# th-usb.net
KiCad netlist of a schematic drawn in EAGLE
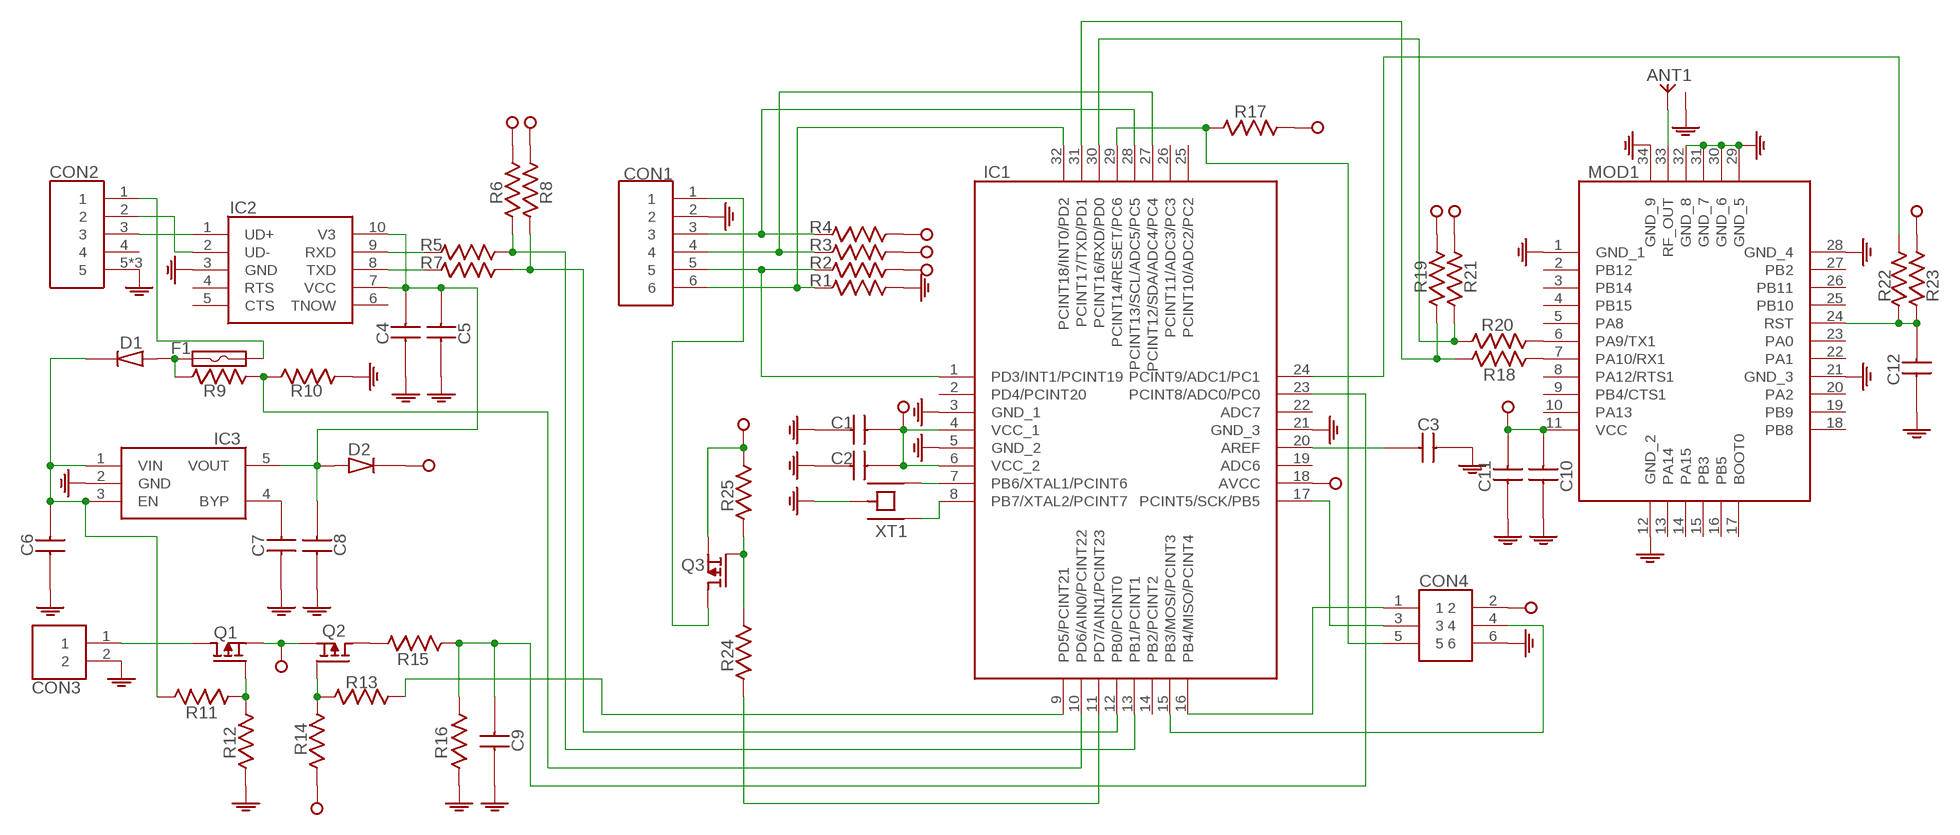
[diagram p0: schematic, sheet 1]

(export (version "E")
  (design (tool "Eeschema 10.0.6"))
  (components
    (comp (ref "ANT1")
      (value "SMA-RF")
      (footprint "eagle-import:SMA-RF")
      (libsource (lib "eagle-import") (part "SMA-RF"))
    )
    (comp (ref "C1")
      (value "CAPACITOR-0805")
      (footprint "eagle-import:0805")
      (libsource (lib "eagle-import") (part "CAPACITOR-0805"))
    )
    (comp (ref "C2")
      (value "CAPACITOR-0603")
      (footprint "eagle-import:0603")
      (libsource (lib "eagle-import") (part "CAPACITOR-0603"))
    )
    (comp (ref "C3")
      (value "CAPACITOR-0603")
      (footprint "eagle-import:0603")
      (libsource (lib "eagle-import") (part "CAPACITOR-0603"))
    )
    (comp (ref "C4")
      (value "CAPACITOR-0805")
      (footprint "eagle-import:0805")
      (libsource (lib "eagle-import") (part "CAPACITOR-0805"))
    )
    (comp (ref "C5")
      (value "CAPACITOR-0603")
      (footprint "eagle-import:0603")
      (libsource (lib "eagle-import") (part "CAPACITOR-0603"))
    )
    (comp (ref "C6")
      (value "CAPACITOR-0805")
      (footprint "eagle-import:0805")
      (libsource (lib "eagle-import") (part "CAPACITOR-0805"))
    )
    (comp (ref "C7")
      (value "CAPACITOR-0603")
      (footprint "eagle-import:0603")
      (libsource (lib "eagle-import") (part "CAPACITOR-0603"))
    )
    (comp (ref "C8")
      (value "CAPACITOR-0805")
      (footprint "eagle-import:0805")
      (libsource (lib "eagle-import") (part "CAPACITOR-0805"))
    )
    (comp (ref "C9")
      (value "CAPACITOR-0603")
      (footprint "eagle-import:0603")
      (libsource (lib "eagle-import") (part "CAPACITOR-0603"))
    )
    (comp (ref "C10")
      (value "CAPACITOR-0805")
      (footprint "eagle-import:0805")
      (libsource (lib "eagle-import") (part "CAPACITOR-0805"))
    )
    (comp (ref "C11")
      (value "CAPACITOR-0603")
      (footprint "eagle-import:0603")
      (libsource (lib "eagle-import") (part "CAPACITOR-0603"))
    )
    (comp (ref "C12")
      (value "CAPACITOR-0603")
      (footprint "eagle-import:0603")
      (libsource (lib "eagle-import") (part "CAPACITOR-0603"))
    )
    (comp (ref "CON1")
      (value "CON-6P-3_81-PLUG")
      (footprint "eagle-import:CON-6P-3_81-PLUG")
      (libsource (lib "eagle-import") (part "CON-6P-3_81-PLUG"))
    )
    (comp (ref "CON2")
      (value "USB-MICRO-DIP-VER")
      (footprint "eagle-import:USB-MICRO-DIP-VER")
      (libsource (lib "eagle-import") (part "USB-MICRO-DIP-VER"))
    )
    (comp (ref "CON3")
      (value "JST-PH-2-2.0MM")
      (footprint "eagle-import:JST-PH-2-2.0MM")
      (libsource (lib "eagle-import") (part "JST-PH-2-2.0MM"))
    )
    (comp (ref "CON4")
      (value "ISP")
      (footprint "eagle-import:ISP")
      (libsource (lib "eagle-import") (part "ISP"))
    )
    (comp (ref "D1")
      (value "DIODE-SOD123")
      (footprint "eagle-import:SOD123-DIODE")
      (libsource (lib "eagle-import") (part "DIODE-SOD123"))
    )
    (comp (ref "D2")
      (value "DIODE-SOD123")
      (footprint "eagle-import:SOD123-DIODE")
      (libsource (lib "eagle-import") (part "DIODE-SOD123"))
    )
    (comp (ref "F1")
      (value "FUSE-0805")
      (footprint "eagle-import:0805")
      (libsource (lib "eagle-import") (part "FUSE-0805"))
    )
    (comp (ref "IC1")
      (value "ATMEGA328P-AU")
      (footprint "eagle-import:TQFP-32")
      (libsource (lib "eagle-import") (part "ATMEGA328P-AU"))
    )
    (comp (ref "IC2")
      (value "CH340E")
      (footprint "eagle-import:MSOP-10")
      (libsource (lib "eagle-import") (part "CH340E"))
    )
    (comp (ref "IC3")
      (value "MIC5219")
      (footprint "eagle-import:SOT23-5")
      (libsource (lib "eagle-import") (part "MIC5219"))
    )
    (comp (ref "MOD1")
      (value "RAK811")
      (footprint "eagle-import:RAK811")
      (libsource (lib "eagle-import") (part "RAK811"))
    )
    (comp (ref "Q1")
      (value "P-MOSFET")
      (footprint "eagle-import:SOT23-3")
      (libsource (lib "eagle-import") (part "P-MOSFET"))
    )
    (comp (ref "Q2")
      (value "P-MOSFET")
      (footprint "eagle-import:SOT23-3")
      (libsource (lib "eagle-import") (part "P-MOSFET"))
    )
    (comp (ref "Q3")
      (value "P-MOSFET")
      (footprint "eagle-import:SOT23-3")
      (libsource (lib "eagle-import") (part "P-MOSFET"))
    )
    (comp (ref "R1")
      (value "RESISTOR-0603")
      (footprint "eagle-import:0603")
      (libsource (lib "eagle-import") (part "RESISTOR-0603"))
    )
    (comp (ref "R2")
      (value "RESISTOR-0603")
      (footprint "eagle-import:0603")
      (libsource (lib "eagle-import") (part "RESISTOR-0603"))
    )
    (comp (ref "R3")
      (value "RESISTOR-0603")
      (footprint "eagle-import:0603")
      (libsource (lib "eagle-import") (part "RESISTOR-0603"))
    )
    (comp (ref "R4")
      (value "RESISTOR-0603")
      (footprint "eagle-import:0603")
      (libsource (lib "eagle-import") (part "RESISTOR-0603"))
    )
    (comp (ref "R5")
      (value "RESISTOR-0603")
      (footprint "eagle-import:0603")
      (libsource (lib "eagle-import") (part "RESISTOR-0603"))
    )
    (comp (ref "R6")
      (value "RESISTOR-0603")
      (footprint "eagle-import:0603")
      (libsource (lib "eagle-import") (part "RESISTOR-0603"))
    )
    (comp (ref "R7")
      (value "RESISTOR-0603")
      (footprint "eagle-import:0603")
      (libsource (lib "eagle-import") (part "RESISTOR-0603"))
    )
    (comp (ref "R8")
      (value "RESISTOR-0603")
      (footprint "eagle-import:0603")
      (libsource (lib "eagle-import") (part "RESISTOR-0603"))
    )
    (comp (ref "R9")
      (value "RESISTOR-0603")
      (footprint "eagle-import:0603")
      (libsource (lib "eagle-import") (part "RESISTOR-0603"))
    )
    (comp (ref "R10")
      (value "RESISTOR-0603")
      (footprint "eagle-import:0603")
      (libsource (lib "eagle-import") (part "RESISTOR-0603"))
    )
    (comp (ref "R11")
      (value "RESISTOR-0603")
      (footprint "eagle-import:0603")
      (libsource (lib "eagle-import") (part "RESISTOR-0603"))
    )
    (comp (ref "R12")
      (value "RESISTOR-0603")
      (footprint "eagle-import:0603")
      (libsource (lib "eagle-import") (part "RESISTOR-0603"))
    )
    (comp (ref "R13")
      (value "RESISTOR-0603")
      (footprint "eagle-import:0603")
      (libsource (lib "eagle-import") (part "RESISTOR-0603"))
    )
    (comp (ref "R14")
      (value "RESISTOR-0603")
      (footprint "eagle-import:0603")
      (libsource (lib "eagle-import") (part "RESISTOR-0603"))
    )
    (comp (ref "R15")
      (value "RESISTOR-0603")
      (footprint "eagle-import:0603")
      (libsource (lib "eagle-import") (part "RESISTOR-0603"))
    )
    (comp (ref "R16")
      (value "RESISTOR-0603")
      (footprint "eagle-import:0603")
      (libsource (lib "eagle-import") (part "RESISTOR-0603"))
    )
    (comp (ref "R17")
      (value "RESISTOR-0603")
      (footprint "eagle-import:0603")
      (libsource (lib "eagle-import") (part "RESISTOR-0603"))
    )
    (comp (ref "R18")
      (value "RESISTOR-0603")
      (footprint "eagle-import:0603")
      (libsource (lib "eagle-import") (part "RESISTOR-0603"))
    )
    (comp (ref "R19")
      (value "RESISTOR-0603")
      (footprint "eagle-import:0603")
      (libsource (lib "eagle-import") (part "RESISTOR-0603"))
    )
    (comp (ref "R20")
      (value "RESISTOR-0603")
      (footprint "eagle-import:0603")
      (libsource (lib "eagle-import") (part "RESISTOR-0603"))
    )
    (comp (ref "R21")
      (value "RESISTOR-0603")
      (footprint "eagle-import:0603")
      (libsource (lib "eagle-import") (part "RESISTOR-0603"))
    )
    (comp (ref "R22")
      (value "RESISTOR-0603")
      (footprint "eagle-import:0603")
      (libsource (lib "eagle-import") (part "RESISTOR-0603"))
    )
    (comp (ref "R23")
      (value "RESISTOR-0603")
      (footprint "eagle-import:0603")
      (libsource (lib "eagle-import") (part "RESISTOR-0603"))
    )
    (comp (ref "R24")
      (value "RESISTOR-0603")
      (footprint "eagle-import:0603")
      (libsource (lib "eagle-import") (part "RESISTOR-0603"))
    )
    (comp (ref "R25")
      (value "RESISTOR-0603")
      (footprint "eagle-import:0603")
      (libsource (lib "eagle-import") (part "RESISTOR-0603"))
    )
    (comp (ref "XT1")
      (value "RESONATOR-3215")
      (footprint "eagle-import:RESONATOR-3215")
      (libsource (lib "eagle-import") (part "RESONATOR-3215"))
    )
  )
  (nets
    (net (code "1") (name "/PD4{slash}PCINT20") (class "Default")
      (node (ref "IC1") (pin "2") (pinfunction "PD4/PCINT20_2") (pintype "power_in"))
    )
    (net (code "2") (name "GND") (class "Default")
      (node (ref "ANT1") (pin "2") (pinfunction "GND_2") (pintype "power_in"))
      (node (ref "ANT1") (pin "3") (pinfunction "GND_3") (pintype "power_in"))
      (node (ref "ANT1") (pin "4") (pinfunction "GND_4") (pintype "power_in"))
      (node (ref "ANT1") (pin "5") (pinfunction "GND_5") (pintype "power_in"))
      (node (ref "C1") (pin "1") (pinfunction "1_1") (pintype "passive"))
      (node (ref "C10") (pin "1") (pinfunction "1_1") (pintype "passive"))
      (node (ref "C11") (pin "1") (pinfunction "1_1") (pintype "passive"))
      (node (ref "C12") (pin "1") (pinfunction "1_1") (pintype "passive"))
      (node (ref "C2") (pin "1") (pinfunction "1_1") (pintype "passive"))
      (node (ref "C3") (pin "2") (pinfunction "2_2") (pintype "passive"))
      (node (ref "C4") (pin "1") (pinfunction "1_1") (pintype "passive"))
      (node (ref "C5") (pin "1") (pinfunction "1_1") (pintype "passive"))
      (node (ref "C6") (pin "1") (pinfunction "1_1") (pintype "passive"))
      (node (ref "C7") (pin "2") (pinfunction "2_2") (pintype "passive"))
      (node (ref "C8") (pin "1") (pinfunction "1_1") (pintype "passive"))
      (node (ref "C9") (pin "1") (pinfunction "1_1") (pintype "passive"))
      (node (ref "CON1") (pin "2") (pinfunction "2_2") (pintype "bidirectional"))
      (node (ref "CON2") (pin "5") (pinfunction "5_5") (pintype "bidirectional"))
      (node (ref "CON2") (pin "6") (pinfunction "5_6") (pintype "bidirectional"))
      (node (ref "CON2") (pin "7") (pinfunction "5_7") (pintype "bidirectional"))
      (node (ref "CON3") (pin "2") (pinfunction "2_2") (pintype "bidirectional"))
      (node (ref "CON4") (pin "6") (pinfunction "6_6") (pintype "power_in"))
      (node (ref "IC1") (pin "21") (pinfunction "GND_3_21") (pintype "power_in"))
      (node (ref "IC1") (pin "3") (pinfunction "GND_1_3") (pintype "power_in"))
      (node (ref "IC1") (pin "5") (pinfunction "GND_2_5") (pintype "power_in"))
      (node (ref "IC2") (pin "3") (pinfunction "GND_3") (pintype "power_in"))
      (node (ref "IC3") (pin "2") (pinfunction "GND_2") (pintype "power_in"))
      (node (ref "MOD1") (pin "1") (pinfunction "GND_1_1") (pintype "power_in"))
      (node (ref "MOD1") (pin "12") (pinfunction "GND_2_12") (pintype "power_in"))
      (node (ref "MOD1") (pin "21") (pinfunction "GND_3_21") (pintype "power_in"))
      (node (ref "MOD1") (pin "28") (pinfunction "GND_4_28") (pintype "power_in"))
      (node (ref "MOD1") (pin "29") (pinfunction "GND_5_29") (pintype "power_in"))
      (node (ref "MOD1") (pin "30") (pinfunction "GND_6_30") (pintype "power_in"))
      (node (ref "MOD1") (pin "31") (pinfunction "GND_7_31") (pintype "power_in"))
      (node (ref "MOD1") (pin "32") (pinfunction "GND_8_32") (pintype "power_in"))
      (node (ref "MOD1") (pin "34") (pinfunction "GND_9_34") (pintype "power_in"))
      (node (ref "R1") (pin "2") (pinfunction "2_2") (pintype "passive"))
      (node (ref "R10") (pin "1") (pinfunction "1_1") (pintype "passive"))
      (node (ref "R12") (pin "1") (pinfunction "1_1") (pintype "passive"))
      (node (ref "R16") (pin "1") (pinfunction "1_1") (pintype "passive"))
      (node (ref "XT1") (pin "3") (pinfunction "3_3") (pintype "power_in"))
    )
    (net (code "3") (name "Net-(ANT1-ANT)") (class "Default")
      (node (ref "ANT1") (pin "1") (pinfunction "ANT_1") (pintype "bidirectional"))
      (node (ref "MOD1") (pin "33") (pinfunction "RF_OUT_33") (pintype "bidirectional"))
    )
    (net (code "4") (name "Net-(CON2-Pad1)") (class "Default")
      (node (ref "CON2") (pin "1") (pinfunction "1_1") (pintype "bidirectional"))
      (node (ref "F1") (pin "1") (pinfunction "1_1") (pintype "passive"))
    )
    (net (code "5") (name "Net-(D1-A)") (class "Default")
      (node (ref "D1") (pin "2") (pinfunction "A_2") (pintype "bidirectional"))
      (node (ref "F1") (pin "2") (pinfunction "2_2") (pintype "passive"))
      (node (ref "R9") (pin "1") (pinfunction "1_1") (pintype "passive"))
    )
    (net (code "6") (name "Net-(D1-K)") (class "Default")
      (node (ref "C6") (pin "2") (pinfunction "2_2") (pintype "passive"))
      (node (ref "D1") (pin "1") (pinfunction "K_1") (pintype "bidirectional"))
      (node (ref "IC3") (pin "1") (pinfunction "VIN_1") (pintype "power_in"))
      (node (ref "IC3") (pin "3") (pinfunction "EN_3") (pintype "input"))
      (node (ref "R11") (pin "2") (pinfunction "2_2") (pintype "passive"))
    )
    (net (code "7") (name "Net-(D2-A)") (class "Default")
      (node (ref "C4") (pin "2") (pinfunction "2_2") (pintype "passive"))
      (node (ref "C5") (pin "2") (pinfunction "2_2") (pintype "passive"))
      (node (ref "C8") (pin "2") (pinfunction "2_2") (pintype "passive"))
      (node (ref "D2") (pin "2") (pinfunction "A_2") (pintype "bidirectional"))
      (node (ref "IC2") (pin "10") (pinfunction "V3_10") (pintype "power_in"))
      (node (ref "IC2") (pin "7") (pinfunction "VCC_7") (pintype "power_in"))
      (node (ref "IC3") (pin "5") (pinfunction "VOUT_5") (pintype "power_in"))
    )
    (net (code "8") (name "Net-(IC1-AREF)") (class "Default")
      (node (ref "C3") (pin "1") (pinfunction "1_1") (pintype "passive"))
      (node (ref "IC1") (pin "20") (pinfunction "AREF_20") (pintype "bidirectional"))
    )
    (net (code "9") (name "Net-(IC1-PB0{slash}PCINT0)") (class "Default")
      (node (ref "IC1") (pin "12") (pinfunction "PB0/PCINT0_12") (pintype "bidirectional"))
      (node (ref "R7") (pin "2") (pinfunction "2_2") (pintype "passive"))
      (node (ref "R8") (pin "1") (pinfunction "1_1") (pintype "passive"))
    )
    (net (code "10") (name "Net-(IC1-PB1{slash}PCINT1)") (class "Default")
      (node (ref "IC1") (pin "13") (pinfunction "PB1/PCINT1_13") (pintype "bidirectional"))
      (node (ref "R5") (pin "2") (pinfunction "2_2") (pintype "passive"))
      (node (ref "R6") (pin "1") (pinfunction "1_1") (pintype "passive"))
    )
    (net (code "11") (name "Net-(IC1-PB3{slash}MOSI{slash}PCINT3)") (class "Default")
      (node (ref "CON4") (pin "4") (pinfunction "4_4") (pintype "bidirectional"))
      (node (ref "IC1") (pin "15") (pinfunction "PB3/MOSI/PCINT3_15") (pintype "bidirectional"))
    )
    (net (code "12") (name "Net-(IC1-PB4{slash}MISO{slash}PCINT4)") (class "Default")
      (node (ref "CON4") (pin "1") (pinfunction "1_1") (pintype "bidirectional"))
      (node (ref "IC1") (pin "16") (pinfunction "PB4/MISO/PCINT4_16") (pintype "bidirectional"))
    )
    (net (code "13") (name "Net-(IC1-PB6{slash}XTAL1{slash}PCINT6)") (class "Default")
      (node (ref "IC1") (pin "7") (pinfunction "PB6/XTAL1/PCINT6_7") (pintype "bidirectional"))
      (node (ref "XT1") (pin "1") (pinfunction "1_1") (pintype "bidirectional"))
    )
    (net (code "14") (name "Net-(IC1-PB7{slash}XTAL2{slash}PCINT7)") (class "Default")
      (node (ref "IC1") (pin "8") (pinfunction "PB7/XTAL2/PCINT7_8") (pintype "bidirectional"))
      (node (ref "XT1") (pin "2") (pinfunction "2_2") (pintype "bidirectional"))
    )
    (net (code "15") (name "Net-(IC1-PCINT5{slash}SCK{slash}PB5)") (class "Default")
      (node (ref "CON4") (pin "3") (pinfunction "3_3") (pintype "bidirectional"))
      (node (ref "IC1") (pin "17") (pinfunction "PCINT5/SCK/PB5_17") (pintype "bidirectional"))
    )
    (net (code "16") (name "Net-(IC1-PCINT8{slash}ADC0{slash}PC0)") (class "Default")
      (node (ref "C9") (pin "2") (pinfunction "2_2") (pintype "passive"))
      (node (ref "IC1") (pin "23") (pinfunction "PCINT8/ADC0/PC0_23") (pintype "bidirectional"))
      (node (ref "R15") (pin "2") (pinfunction "2_2") (pintype "passive"))
      (node (ref "R16") (pin "2") (pinfunction "2_2") (pintype "passive"))
    )
    (net (code "17") (name "Net-(IC1-PCINT9{slash}ADC1{slash}PC1)") (class "Default")
      (node (ref "IC1") (pin "24") (pinfunction "PCINT9/ADC1/PC1_24") (pintype "bidirectional"))
      (node (ref "R22") (pin "2") (pinfunction "2_2") (pintype "passive"))
    )
    (net (code "18") (name "Net-(IC1-PCINT12{slash}SDA{slash}ADC4{slash}PC4)") (class "Default")
      (node (ref "CON1") (pin "4") (pinfunction "4_4") (pintype "bidirectional"))
      (node (ref "IC1") (pin "27") (pinfunction "PCINT12/SDA/ADC4/PC4_27") (pintype "bidirectional"))
      (node (ref "R3") (pin "1") (pinfunction "1_1") (pintype "passive"))
    )
    (net (code "19") (name "Net-(IC1-PCINT13{slash}SCL{slash}ADC5{slash}PC5)") (class "Default")
      (node (ref "CON1") (pin "3") (pinfunction "3_3") (pintype "bidirectional"))
      (node (ref "IC1") (pin "28") (pinfunction "PCINT13/SCL/ADC5/PC5_28") (pintype "bidirectional"))
      (node (ref "R4") (pin "1") (pinfunction "1_1") (pintype "passive"))
    )
    (net (code "20") (name "Net-(IC1-PCINT14{slash}RESET{slash}PC6)") (class "Default")
      (node (ref "CON4") (pin "5") (pinfunction "5_5") (pintype "bidirectional"))
      (node (ref "IC1") (pin "29") (pinfunction "PCINT14/RESET/PC6_29") (pintype "bidirectional"))
      (node (ref "R17") (pin "1") (pinfunction "1_1") (pintype "passive"))
    )
    (net (code "21") (name "Net-(IC1-PCINT16{slash}RXD{slash}PD0)") (class "Default")
      (node (ref "IC1") (pin "30") (pinfunction "PCINT16/RXD/PD0_30") (pintype "bidirectional"))
      (node (ref "R20") (pin "1") (pinfunction "1_1") (pintype "passive"))
      (node (ref "R21") (pin "1") (pinfunction "1_1") (pintype "passive"))
    )
    (net (code "22") (name "Net-(IC1-PCINT17{slash}TXD{slash}PD1)") (class "Default")
      (node (ref "IC1") (pin "31") (pinfunction "PCINT17/TXD/PD1_31") (pintype "bidirectional"))
      (node (ref "R18") (pin "1") (pinfunction "1_1") (pintype "passive"))
      (node (ref "R19") (pin "1") (pinfunction "1_1") (pintype "passive"))
    )
    (net (code "23") (name "Net-(IC1-PCINT18{slash}INT0{slash}PD2)") (class "Default")
      (node (ref "CON1") (pin "6") (pinfunction "6_6") (pintype "bidirectional"))
      (node (ref "IC1") (pin "32") (pinfunction "PCINT18/INT0/PD2_32") (pintype "bidirectional"))
      (node (ref "R1") (pin "1") (pinfunction "1_1") (pintype "passive"))
    )
    (net (code "24") (name "Net-(IC1-PD3{slash}INT1{slash}PCINT19)") (class "Default")
      (node (ref "CON1") (pin "5") (pinfunction "5_5") (pintype "bidirectional"))
      (node (ref "IC1") (pin "1") (pinfunction "PD3/INT1/PCINT19_1") (pintype "bidirectional"))
      (node (ref "R2") (pin "1") (pinfunction "1_1") (pintype "passive"))
    )
    (net (code "25") (name "Net-(IC1-PD5{slash}PCINT21)") (class "Default")
      (node (ref "IC1") (pin "9") (pinfunction "PD5/PCINT21_9") (pintype "bidirectional"))
      (node (ref "R13") (pin "2") (pinfunction "2_2") (pintype "passive"))
    )
    (net (code "26") (name "Net-(IC1-PD6{slash}AIN0{slash}PCINT22)") (class "Default")
      (node (ref "IC1") (pin "10") (pinfunction "PD6/AIN0/PCINT22_10") (pintype "bidirectional"))
      (node (ref "R10") (pin "2") (pinfunction "2_2") (pintype "passive"))
      (node (ref "R9") (pin "2") (pinfunction "2_2") (pintype "passive"))
    )
    (net (code "27") (name "Net-(IC1-PD7{slash}AIN1{slash}PCINT23)") (class "Default")
      (node (ref "IC1") (pin "11") (pinfunction "PD7/AIN1/PCINT23_11") (pintype "bidirectional"))
      (node (ref "R24") (pin "1") (pinfunction "1_1") (pintype "passive"))
    )
    (net (code "28") (name "Net-(IC2-RXD)") (class "Default")
      (node (ref "IC2") (pin "9") (pinfunction "RXD_9") (pintype "bidirectional"))
      (node (ref "R5") (pin "1") (pinfunction "1_1") (pintype "passive"))
    )
    (net (code "29") (name "Net-(IC2-TXD)") (class "Default")
      (node (ref "IC2") (pin "8") (pinfunction "TXD_8") (pintype "bidirectional"))
      (node (ref "R7") (pin "1") (pinfunction "1_1") (pintype "passive"))
    )
    (net (code "30") (name "Net-(IC2-UD+)") (class "Default")
      (node (ref "CON2") (pin "3") (pinfunction "3_3") (pintype "bidirectional"))
      (node (ref "IC2") (pin "1") (pinfunction "UD+_1") (pintype "power_in"))
    )
    (net (code "31") (name "Net-(IC2-UD-)") (class "Default")
      (node (ref "CON2") (pin "2") (pinfunction "2_2") (pintype "bidirectional"))
      (node (ref "IC2") (pin "2") (pinfunction "UD-_2") (pintype "power_in"))
    )
    (net (code "32") (name "Net-(IC3-BYP)") (class "Default")
      (node (ref "C7") (pin "1") (pinfunction "1_1") (pintype "passive"))
      (node (ref "IC3") (pin "4") (pinfunction "BYP_4") (pintype "output"))
    )
    (net (code "33") (name "Net-(MOD1-PA9{slash}TX1)") (class "Default")
      (node (ref "MOD1") (pin "6") (pinfunction "PA9/TX1_6") (pintype "bidirectional"))
      (node (ref "R20") (pin "2") (pinfunction "2_2") (pintype "passive"))
    )
    (net (code "34") (name "Net-(MOD1-PA10{slash}RX1)") (class "Default")
      (node (ref "MOD1") (pin "7") (pinfunction "PA10/RX1_7") (pintype "bidirectional"))
      (node (ref "R18") (pin "2") (pinfunction "2_2") (pintype "passive"))
    )
    (net (code "35") (name "Net-(MOD1-RST)") (class "Default")
      (node (ref "C12") (pin "2") (pinfunction "2_2") (pintype "passive"))
      (node (ref "MOD1") (pin "24") (pinfunction "RST_24") (pintype "bidirectional"))
      (node (ref "R22") (pin "1") (pinfunction "1_1") (pintype "passive"))
      (node (ref "R23") (pin "1") (pinfunction "1_1") (pintype "passive"))
    )
    (net (code "36") (name "Net-(Q1-D)") (class "Default")
      (node (ref "CON3") (pin "1") (pinfunction "1_1") (pintype "bidirectional"))
      (node (ref "Q1") (pin "3") (pinfunction "D_3") (pintype "bidirectional"))
    )
    (net (code "37") (name "Net-(Q1-G)") (class "Default")
      (node (ref "Q1") (pin "1") (pinfunction "G_1") (pintype "bidirectional"))
      (node (ref "R11") (pin "1") (pinfunction "1_1") (pintype "passive"))
      (node (ref "R12") (pin "2") (pinfunction "2_2") (pintype "passive"))
    )
    (net (code "38") (name "Net-(Q2-D)") (class "Default")
      (node (ref "Q2") (pin "3") (pinfunction "D_3") (pintype "bidirectional"))
      (node (ref "R15") (pin "1") (pinfunction "1_1") (pintype "passive"))
    )
    (net (code "39") (name "Net-(Q2-G)") (class "Default")
      (node (ref "Q2") (pin "1") (pinfunction "G_1") (pintype "bidirectional"))
      (node (ref "R13") (pin "1") (pinfunction "1_1") (pintype "passive"))
      (node (ref "R14") (pin "2") (pinfunction "2_2") (pintype "passive"))
    )
    (net (code "40") (name "Net-(Q3-D)") (class "Default")
      (node (ref "CON1") (pin "1") (pinfunction "1_1") (pintype "bidirectional"))
      (node (ref "Q3") (pin "3") (pinfunction "D_3") (pintype "bidirectional"))
    )
    (net (code "41") (name "Net-(Q3-G)") (class "Default")
      (node (ref "Q3") (pin "1") (pinfunction "G_1") (pintype "bidirectional"))
      (node (ref "R24") (pin "2") (pinfunction "2_2") (pintype "passive"))
      (node (ref "R25") (pin "1") (pinfunction "1_1") (pintype "passive"))
    )
    (net (code "42") (name "VCC") (class "Default")
      (node (ref "C1") (pin "2") (pinfunction "2_2") (pintype "passive"))
      (node (ref "C10") (pin "2") (pinfunction "2_2") (pintype "passive"))
      (node (ref "C11") (pin "2") (pinfunction "2_2") (pintype "passive"))
      (node (ref "C2") (pin "2") (pinfunction "2_2") (pintype "passive"))
      (node (ref "CON4") (pin "2") (pinfunction "2_2") (pintype "power_in"))
      (node (ref "D2") (pin "1") (pinfunction "K_1") (pintype "bidirectional"))
      (node (ref "IC1") (pin "18") (pinfunction "AVCC_18") (pintype "power_in"))
      (node (ref "IC1") (pin "4") (pinfunction "VCC_1_4") (pintype "power_in"))
      (node (ref "IC1") (pin "6") (pinfunction "VCC_2_6") (pintype "power_in"))
      (node (ref "MOD1") (pin "11") (pinfunction "VCC_11") (pintype "power_in"))
      (node (ref "Q1") (pin "2") (pinfunction "S_2") (pintype "bidirectional"))
      (node (ref "Q2") (pin "2") (pinfunction "S_2") (pintype "bidirectional"))
      (node (ref "Q3") (pin "2") (pinfunction "S_2") (pintype "bidirectional"))
      (node (ref "R14") (pin "1") (pinfunction "1_1") (pintype "passive"))
      (node (ref "R17") (pin "2") (pinfunction "2_2") (pintype "passive"))
      (node (ref "R19") (pin "2") (pinfunction "2_2") (pintype "passive"))
      (node (ref "R2") (pin "2") (pinfunction "2_2") (pintype "passive"))
      (node (ref "R21") (pin "2") (pinfunction "2_2") (pintype "passive"))
      (node (ref "R23") (pin "2") (pinfunction "2_2") (pintype "passive"))
      (node (ref "R25") (pin "2") (pinfunction "2_2") (pintype "passive"))
      (node (ref "R3") (pin "2") (pinfunction "2_2") (pintype "passive"))
      (node (ref "R4") (pin "2") (pinfunction "2_2") (pintype "passive"))
      (node (ref "R6") (pin "2") (pinfunction "2_2") (pintype "passive"))
      (node (ref "R8") (pin "2") (pinfunction "2_2") (pintype "passive"))
    )
    (net (code "43") (name "unconnected-(CON2-Pad4)") (class "Default")
      (node (ref "CON2") (pin "4") (pinfunction "4_4") (pintype "bidirectional"))
    )
    (net (code "44") (name "unconnected-(IC1-ADC6-Pad19)") (class "Default")
      (node (ref "IC1") (pin "19") (pinfunction "ADC6_19") (pintype "bidirectional"))
    )
    (net (code "45") (name "unconnected-(IC1-ADC7-Pad22)") (class "Default")
      (node (ref "IC1") (pin "22") (pinfunction "ADC7_22") (pintype "bidirectional"))
    )
    (net (code "46") (name "unconnected-(IC1-PB2{slash}PCINT2-Pad14)") (class "Default")
      (node (ref "IC1") (pin "14") (pinfunction "PB2/PCINT2_14") (pintype "bidirectional"))
    )
    (net (code "47") (name "unconnected-(IC1-PCINT10{slash}ADC2{slash}PC2-Pad25)") (class "Default")
      (node (ref "IC1") (pin "25") (pinfunction "PCINT10/ADC2/PC2_25") (pintype "bidirectional"))
    )
    (net (code "48") (name "unconnected-(IC1-PCINT11{slash}ADC3{slash}PC3-Pad26)") (class "Default")
      (node (ref "IC1") (pin "26") (pinfunction "PCINT11/ADC3/PC3_26") (pintype "bidirectional"))
    )
    (net (code "49") (name "unconnected-(IC2-CTS-Pad5)") (class "Default")
      (node (ref "IC2") (pin "5") (pinfunction "CTS_5") (pintype "bidirectional"))
    )
    (net (code "50") (name "unconnected-(IC2-RTS-Pad4)") (class "Default")
      (node (ref "IC2") (pin "4") (pinfunction "RTS_4") (pintype "bidirectional"))
    )
    (net (code "51") (name "unconnected-(IC2-TNOW-Pad6)") (class "Default")
      (node (ref "IC2") (pin "6") (pinfunction "TNOW_6") (pintype "bidirectional"))
    )
    (net (code "52") (name "unconnected-(MOD1-BOOT0-Pad17)") (class "Default")
      (node (ref "MOD1") (pin "17") (pinfunction "BOOT0_17") (pintype "bidirectional"))
    )
    (net (code "53") (name "unconnected-(MOD1-PA0-Pad23)") (class "Default")
      (node (ref "MOD1") (pin "23") (pinfunction "PA0_23") (pintype "bidirectional"))
    )
    (net (code "54") (name "unconnected-(MOD1-PA1-Pad22)") (class "Default")
      (node (ref "MOD1") (pin "22") (pinfunction "PA1_22") (pintype "bidirectional"))
    )
    (net (code "55") (name "unconnected-(MOD1-PA2-Pad20)") (class "Default")
      (node (ref "MOD1") (pin "20") (pinfunction "PA2_20") (pintype "bidirectional"))
    )
    (net (code "56") (name "unconnected-(MOD1-PA8-Pad5)") (class "Default")
      (node (ref "MOD1") (pin "5") (pinfunction "PA8_5") (pintype "bidirectional"))
    )
    (net (code "57") (name "unconnected-(MOD1-PA12{slash}RTS1-Pad8)") (class "Default")
      (node (ref "MOD1") (pin "8") (pinfunction "PA12/RTS1_8") (pintype "bidirectional"))
    )
    (net (code "58") (name "unconnected-(MOD1-PA13-Pad10)") (class "Default")
      (node (ref "MOD1") (pin "10") (pinfunction "PA13_10") (pintype "bidirectional"))
    )
    (net (code "59") (name "unconnected-(MOD1-PA14-Pad13)") (class "Default")
      (node (ref "MOD1") (pin "13") (pinfunction "PA14_13") (pintype "bidirectional"))
    )
    (net (code "60") (name "unconnected-(MOD1-PA15-Pad14)") (class "Default")
      (node (ref "MOD1") (pin "14") (pinfunction "PA15_14") (pintype "bidirectional"))
    )
    (net (code "61") (name "unconnected-(MOD1-PB2-Pad27)") (class "Default")
      (node (ref "MOD1") (pin "27") (pinfunction "PB2_27") (pintype "bidirectional"))
    )
    (net (code "62") (name "unconnected-(MOD1-PB3-Pad15)") (class "Default")
      (node (ref "MOD1") (pin "15") (pinfunction "PB3_15") (pintype "bidirectional"))
    )
    (net (code "63") (name "unconnected-(MOD1-PB4{slash}CTS1-Pad9)") (class "Default")
      (node (ref "MOD1") (pin "9") (pinfunction "PB4/CTS1_9") (pintype "bidirectional"))
    )
    (net (code "64") (name "unconnected-(MOD1-PB5-Pad16)") (class "Default")
      (node (ref "MOD1") (pin "16") (pinfunction "PB5_16") (pintype "bidirectional"))
    )
    (net (code "65") (name "unconnected-(MOD1-PB8-Pad18)") (class "Default")
      (node (ref "MOD1") (pin "18") (pinfunction "PB8_18") (pintype "bidirectional"))
    )
    (net (code "66") (name "unconnected-(MOD1-PB9-Pad19)") (class "Default")
      (node (ref "MOD1") (pin "19") (pinfunction "PB9_19") (pintype "bidirectional"))
    )
    (net (code "67") (name "unconnected-(MOD1-PB10-Pad25)") (class "Default")
      (node (ref "MOD1") (pin "25") (pinfunction "PB10_25") (pintype "bidirectional"))
    )
    (net (code "68") (name "unconnected-(MOD1-PB11-Pad26)") (class "Default")
      (node (ref "MOD1") (pin "26") (pinfunction "PB11_26") (pintype "bidirectional"))
    )
    (net (code "69") (name "unconnected-(MOD1-PB12-Pad2)") (class "Default")
      (node (ref "MOD1") (pin "2") (pinfunction "PB12_2") (pintype "bidirectional"))
    )
    (net (code "70") (name "unconnected-(MOD1-PB14-Pad3)") (class "Default")
      (node (ref "MOD1") (pin "3") (pinfunction "PB14_3") (pintype "bidirectional"))
    )
    (net (code "71") (name "unconnected-(MOD1-PB15-Pad4)") (class "Default")
      (node (ref "MOD1") (pin "4") (pinfunction "PB15_4") (pintype "bidirectional"))
    )
  )
)
